# 4bit_ram.net
KiCad netlist of a schematic drawn in EAGLE
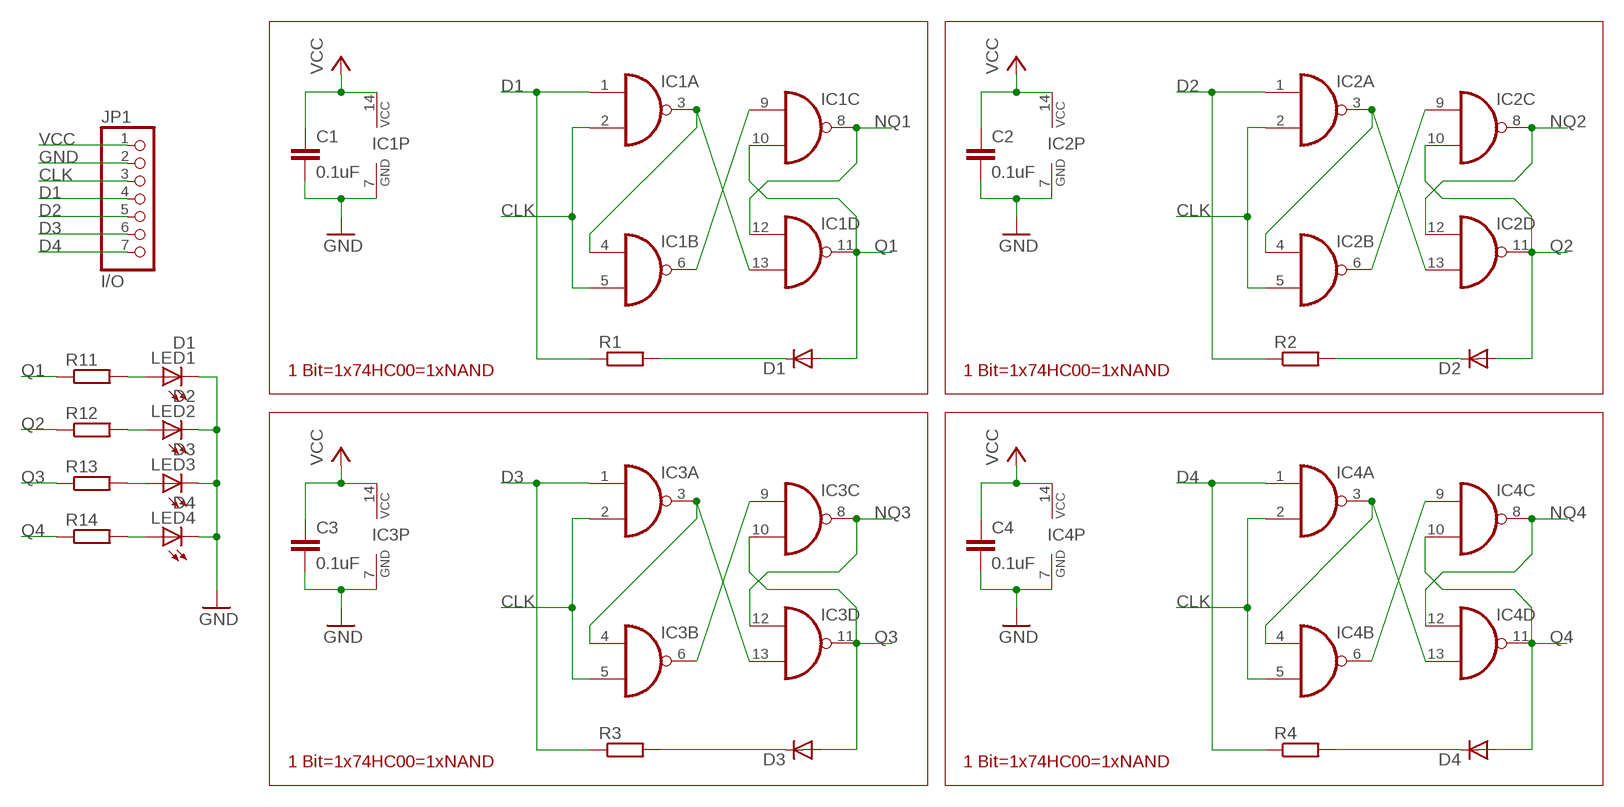
[diagram p0: schematic, sheet 1]

(export (version "E")
  (design (tool "Eeschema 10.0.6"))
  (components
    (comp (ref "C1")
      (value "0.1uF")
      (footprint "eagle-import:C025-025X050")
      (libsource (lib "eagle-import") (part "C-EU025-025X050"))
    )
    (comp (ref "C2")
      (value "0.1uF")
      (footprint "eagle-import:C025-025X050")
      (libsource (lib "eagle-import") (part "C-EU025-025X050"))
    )
    (comp (ref "C3")
      (value "0.1uF")
      (footprint "eagle-import:C025-025X050")
      (libsource (lib "eagle-import") (part "C-EU025-025X050"))
    )
    (comp (ref "C4")
      (value "0.1uF")
      (footprint "eagle-import:C025-025X050")
      (libsource (lib "eagle-import") (part "C-EU025-025X050"))
    )
    (comp (ref "D1")
      (value "1N4148DO35-7")
      (footprint "eagle-import:DO35-7")
      (libsource (lib "eagle-import") (part "1N4148DO35-7"))
    )
    (comp (ref "D2")
      (value "1N4148DO35-7")
      (footprint "eagle-import:DO35-7")
      (libsource (lib "eagle-import") (part "1N4148DO35-7"))
    )
    (comp (ref "D3")
      (value "1N4148DO35-7")
      (footprint "eagle-import:DO35-7")
      (libsource (lib "eagle-import") (part "1N4148DO35-7"))
    )
    (comp (ref "D4")
      (value "1N4148DO35-7")
      (footprint "eagle-import:DO35-7")
      (libsource (lib "eagle-import") (part "1N4148DO35-7"))
    )
    (comp (ref "IC1")
      (value "74HC00N")
      (footprint "eagle-import:DIL14")
      (libsource (lib "eagle-import") (part "7400NHC"))
    )
    (comp (ref "IC2")
      (value "74HC00N")
      (footprint "eagle-import:DIL14")
      (libsource (lib "eagle-import") (part "7400NHC"))
    )
    (comp (ref "IC3")
      (value "74HC00N")
      (footprint "eagle-import:DIL14")
      (libsource (lib "eagle-import") (part "7400NHC"))
    )
    (comp (ref "IC4")
      (value "74HC00N")
      (footprint "eagle-import:DIL14")
      (libsource (lib "eagle-import") (part "7400NHC"))
    )
    (comp (ref "JP1")
      (value "I/O")
      (footprint "eagle-import:1X07")
      (libsource (lib "eagle-import") (part "PINHD-1X7"))
    )
    (comp (ref "LED1")
      (value "D1")
      (footprint "eagle-import:LED3MM")
      (libsource (lib "eagle-import") (part "LED3MM"))
    )
    (comp (ref "LED2")
      (value "D2")
      (footprint "eagle-import:LED3MM")
      (libsource (lib "eagle-import") (part "LED3MM"))
    )
    (comp (ref "LED3")
      (value "D3")
      (footprint "eagle-import:LED3MM")
      (libsource (lib "eagle-import") (part "LED3MM"))
    )
    (comp (ref "LED4")
      (value "D4")
      (footprint "eagle-import:LED3MM")
      (libsource (lib "eagle-import") (part "LED3MM"))
    )
    (comp (ref "R1")
      (value "10K")
      (footprint "eagle-import:0204_7")
      (libsource (lib "eagle-import") (part "R-EU_0204/7"))
    )
    (comp (ref "R2")
      (value "10K")
      (footprint "eagle-import:0204_7")
      (libsource (lib "eagle-import") (part "R-EU_0204/7"))
    )
    (comp (ref "R3")
      (value "10K")
      (footprint "eagle-import:0204_7")
      (libsource (lib "eagle-import") (part "R-EU_0204/7"))
    )
    (comp (ref "R4")
      (value "10K")
      (footprint "eagle-import:0204_7")
      (libsource (lib "eagle-import") (part "R-EU_0204/7"))
    )
    (comp (ref "R11")
      (value "470")
      (footprint "eagle-import:0204_7")
      (libsource (lib "eagle-import") (part "R-EU_0204/7"))
    )
    (comp (ref "R12")
      (value "470")
      (footprint "eagle-import:0204_7")
      (libsource (lib "eagle-import") (part "R-EU_0204/7"))
    )
    (comp (ref "R13")
      (value "470")
      (footprint "eagle-import:0204_7")
      (libsource (lib "eagle-import") (part "R-EU_0204/7"))
    )
    (comp (ref "R14")
      (value "470")
      (footprint "eagle-import:0204_7")
      (libsource (lib "eagle-import") (part "R-EU_0204/7"))
    )
  )
  (nets
    (net (code "1") (name "/CLK") (class "Default")
      (node (ref "IC1") (pin "2") (pinfunction "I1_2") (pintype "input"))
      (node (ref "IC1") (pin "5") (pinfunction "I1_5") (pintype "input"))
      (node (ref "IC2") (pin "2") (pinfunction "I1_2") (pintype "input"))
      (node (ref "IC2") (pin "5") (pinfunction "I1_5") (pintype "input"))
      (node (ref "IC3") (pin "2") (pinfunction "I1_2") (pintype "input"))
      (node (ref "IC3") (pin "5") (pinfunction "I1_5") (pintype "input"))
      (node (ref "IC4") (pin "2") (pinfunction "I1_2") (pintype "input"))
      (node (ref "IC4") (pin "5") (pinfunction "I1_5") (pintype "input"))
      (node (ref "JP1") (pin "3") (pinfunction "3_3") (pintype "passive"))
    )
    (net (code "2") (name "/D1") (class "Default")
      (node (ref "IC1") (pin "1") (pinfunction "I0_1") (pintype "input"))
      (node (ref "JP1") (pin "4") (pinfunction "4_4") (pintype "passive"))
      (node (ref "R1") (pin "1") (pinfunction "1_1") (pintype "passive"))
    )
    (net (code "3") (name "/D2") (class "Default")
      (node (ref "IC2") (pin "1") (pinfunction "I0_1") (pintype "input"))
      (node (ref "JP1") (pin "5") (pinfunction "5_5") (pintype "passive"))
      (node (ref "R2") (pin "1") (pinfunction "1_1") (pintype "passive"))
    )
    (net (code "4") (name "/D3") (class "Default")
      (node (ref "IC3") (pin "1") (pinfunction "I0_1") (pintype "input"))
      (node (ref "JP1") (pin "6") (pinfunction "6_6") (pintype "passive"))
      (node (ref "R3") (pin "1") (pinfunction "1_1") (pintype "passive"))
    )
    (net (code "5") (name "/D4") (class "Default")
      (node (ref "IC4") (pin "1") (pinfunction "I0_1") (pintype "input"))
      (node (ref "JP1") (pin "7") (pinfunction "7_7") (pintype "passive"))
      (node (ref "R4") (pin "1") (pinfunction "1_1") (pintype "passive"))
    )
    (net (code "6") (name "/NQ1") (class "Default")
      (node (ref "IC1") (pin "12") (pinfunction "I0_12") (pintype "input"))
      (node (ref "IC1") (pin "8") (pinfunction "O_8") (pintype "output"))
    )
    (net (code "7") (name "/NQ2") (class "Default")
      (node (ref "IC2") (pin "12") (pinfunction "I0_12") (pintype "input"))
      (node (ref "IC2") (pin "8") (pinfunction "O_8") (pintype "output"))
    )
    (net (code "8") (name "/NQ3") (class "Default")
      (node (ref "IC3") (pin "12") (pinfunction "I0_12") (pintype "input"))
      (node (ref "IC3") (pin "8") (pinfunction "O_8") (pintype "output"))
    )
    (net (code "9") (name "/NQ4") (class "Default")
      (node (ref "IC4") (pin "12") (pinfunction "I0_12") (pintype "input"))
      (node (ref "IC4") (pin "8") (pinfunction "O_8") (pintype "output"))
    )
    (net (code "10") (name "/Q1") (class "Default")
      (node (ref "D1") (pin "A") (pinfunction "A_A") (pintype "passive"))
      (node (ref "IC1") (pin "10") (pinfunction "I1_10") (pintype "input"))
      (node (ref "IC1") (pin "11") (pinfunction "O_11") (pintype "output"))
      (node (ref "R11") (pin "1") (pinfunction "1_1") (pintype "passive"))
    )
    (net (code "11") (name "/Q2") (class "Default")
      (node (ref "D2") (pin "A") (pinfunction "A_A") (pintype "passive"))
      (node (ref "IC2") (pin "10") (pinfunction "I1_10") (pintype "input"))
      (node (ref "IC2") (pin "11") (pinfunction "O_11") (pintype "output"))
      (node (ref "R12") (pin "1") (pinfunction "1_1") (pintype "passive"))
    )
    (net (code "12") (name "/Q3") (class "Default")
      (node (ref "D3") (pin "A") (pinfunction "A_A") (pintype "passive"))
      (node (ref "IC3") (pin "10") (pinfunction "I1_10") (pintype "input"))
      (node (ref "IC3") (pin "11") (pinfunction "O_11") (pintype "output"))
      (node (ref "R13") (pin "1") (pinfunction "1_1") (pintype "passive"))
    )
    (net (code "13") (name "/Q4") (class "Default")
      (node (ref "D4") (pin "A") (pinfunction "A_A") (pintype "passive"))
      (node (ref "IC4") (pin "10") (pinfunction "I1_10") (pintype "input"))
      (node (ref "IC4") (pin "11") (pinfunction "O_11") (pintype "output"))
      (node (ref "R14") (pin "1") (pinfunction "1_1") (pintype "passive"))
    )
    (net (code "14") (name "GND") (class "Default")
      (node (ref "C1") (pin "2") (pinfunction "2_2") (pintype "passive"))
      (node (ref "C2") (pin "2") (pinfunction "2_2") (pintype "passive"))
      (node (ref "C3") (pin "2") (pinfunction "2_2") (pintype "passive"))
      (node (ref "C4") (pin "2") (pinfunction "2_2") (pintype "passive"))
      (node (ref "IC1") (pin "7") (pinfunction "GND_7") (pintype "power_in"))
      (node (ref "IC2") (pin "7") (pinfunction "GND_7") (pintype "power_in"))
      (node (ref "IC3") (pin "7") (pinfunction "GND_7") (pintype "power_in"))
      (node (ref "IC4") (pin "7") (pinfunction "GND_7") (pintype "power_in"))
      (node (ref "JP1") (pin "2") (pinfunction "2_2") (pintype "passive"))
      (node (ref "LED1") (pin "K") (pinfunction "C_K") (pintype "passive"))
      (node (ref "LED2") (pin "K") (pinfunction "C_K") (pintype "passive"))
      (node (ref "LED3") (pin "K") (pinfunction "C_K") (pintype "passive"))
      (node (ref "LED4") (pin "K") (pinfunction "C_K") (pintype "passive"))
    )
    (net (code "15") (name "Net-(D1-PadC)") (class "Default")
      (node (ref "D1") (pin "C") (pinfunction "C_C") (pintype "passive"))
      (node (ref "R1") (pin "2") (pinfunction "2_2") (pintype "passive"))
    )
    (net (code "16") (name "Net-(D2-PadC)") (class "Default")
      (node (ref "D2") (pin "C") (pinfunction "C_C") (pintype "passive"))
      (node (ref "R2") (pin "2") (pinfunction "2_2") (pintype "passive"))
    )
    (net (code "17") (name "Net-(D3-PadC)") (class "Default")
      (node (ref "D3") (pin "C") (pinfunction "C_C") (pintype "passive"))
      (node (ref "R3") (pin "2") (pinfunction "2_2") (pintype "passive"))
    )
    (net (code "18") (name "Net-(D4-PadC)") (class "Default")
      (node (ref "D4") (pin "C") (pinfunction "C_C") (pintype "passive"))
      (node (ref "R4") (pin "2") (pinfunction "2_2") (pintype "passive"))
    )
    (net (code "19") (name "Net-(IC1A-O)") (class "Default")
      (node (ref "IC1") (pin "13") (pinfunction "I1_13") (pintype "input"))
      (node (ref "IC1") (pin "3") (pinfunction "O_3") (pintype "output"))
      (node (ref "IC1") (pin "4") (pinfunction "I0_4") (pintype "input"))
    )
    (net (code "20") (name "Net-(IC1B-O)") (class "Default")
      (node (ref "IC1") (pin "6") (pinfunction "O_6") (pintype "output"))
      (node (ref "IC1") (pin "9") (pinfunction "I0_9") (pintype "input"))
    )
    (net (code "21") (name "Net-(IC2A-O)") (class "Default")
      (node (ref "IC2") (pin "13") (pinfunction "I1_13") (pintype "input"))
      (node (ref "IC2") (pin "3") (pinfunction "O_3") (pintype "output"))
      (node (ref "IC2") (pin "4") (pinfunction "I0_4") (pintype "input"))
    )
    (net (code "22") (name "Net-(IC2B-O)") (class "Default")
      (node (ref "IC2") (pin "6") (pinfunction "O_6") (pintype "output"))
      (node (ref "IC2") (pin "9") (pinfunction "I0_9") (pintype "input"))
    )
    (net (code "23") (name "Net-(IC3A-O)") (class "Default")
      (node (ref "IC3") (pin "13") (pinfunction "I1_13") (pintype "input"))
      (node (ref "IC3") (pin "3") (pinfunction "O_3") (pintype "output"))
      (node (ref "IC3") (pin "4") (pinfunction "I0_4") (pintype "input"))
    )
    (net (code "24") (name "Net-(IC3B-O)") (class "Default")
      (node (ref "IC3") (pin "6") (pinfunction "O_6") (pintype "output"))
      (node (ref "IC3") (pin "9") (pinfunction "I0_9") (pintype "input"))
    )
    (net (code "25") (name "Net-(IC4A-O)") (class "Default")
      (node (ref "IC4") (pin "13") (pinfunction "I1_13") (pintype "input"))
      (node (ref "IC4") (pin "3") (pinfunction "O_3") (pintype "output"))
      (node (ref "IC4") (pin "4") (pinfunction "I0_4") (pintype "input"))
    )
    (net (code "26") (name "Net-(IC4B-O)") (class "Default")
      (node (ref "IC4") (pin "6") (pinfunction "O_6") (pintype "output"))
      (node (ref "IC4") (pin "9") (pinfunction "I0_9") (pintype "input"))
    )
    (net (code "27") (name "Net-(LED1-PadA)") (class "Default")
      (node (ref "LED1") (pin "A") (pinfunction "A_A") (pintype "passive"))
      (node (ref "R11") (pin "2") (pinfunction "2_2") (pintype "passive"))
    )
    (net (code "28") (name "Net-(LED2-PadA)") (class "Default")
      (node (ref "LED2") (pin "A") (pinfunction "A_A") (pintype "passive"))
      (node (ref "R12") (pin "2") (pinfunction "2_2") (pintype "passive"))
    )
    (net (code "29") (name "Net-(LED3-PadA)") (class "Default")
      (node (ref "LED3") (pin "A") (pinfunction "A_A") (pintype "passive"))
      (node (ref "R13") (pin "2") (pinfunction "2_2") (pintype "passive"))
    )
    (net (code "30") (name "Net-(LED4-PadA)") (class "Default")
      (node (ref "LED4") (pin "A") (pinfunction "A_A") (pintype "passive"))
      (node (ref "R14") (pin "2") (pinfunction "2_2") (pintype "passive"))
    )
    (net (code "31") (name "VCC") (class "Default")
      (node (ref "C1") (pin "1") (pinfunction "1_1") (pintype "passive"))
      (node (ref "C2") (pin "1") (pinfunction "1_1") (pintype "passive"))
      (node (ref "C3") (pin "1") (pinfunction "1_1") (pintype "passive"))
      (node (ref "C4") (pin "1") (pinfunction "1_1") (pintype "passive"))
      (node (ref "IC1") (pin "14") (pinfunction "VCC_14") (pintype "power_in"))
      (node (ref "IC2") (pin "14") (pinfunction "VCC_14") (pintype "power_in"))
      (node (ref "IC3") (pin "14") (pinfunction "VCC_14") (pintype "power_in"))
      (node (ref "IC4") (pin "14") (pinfunction "VCC_14") (pintype "power_in"))
      (node (ref "JP1") (pin "1") (pinfunction "1_1") (pintype "passive"))
    )
  )
)
